# tube_power.net
KiCad netlist of a schematic drawn in EAGLE
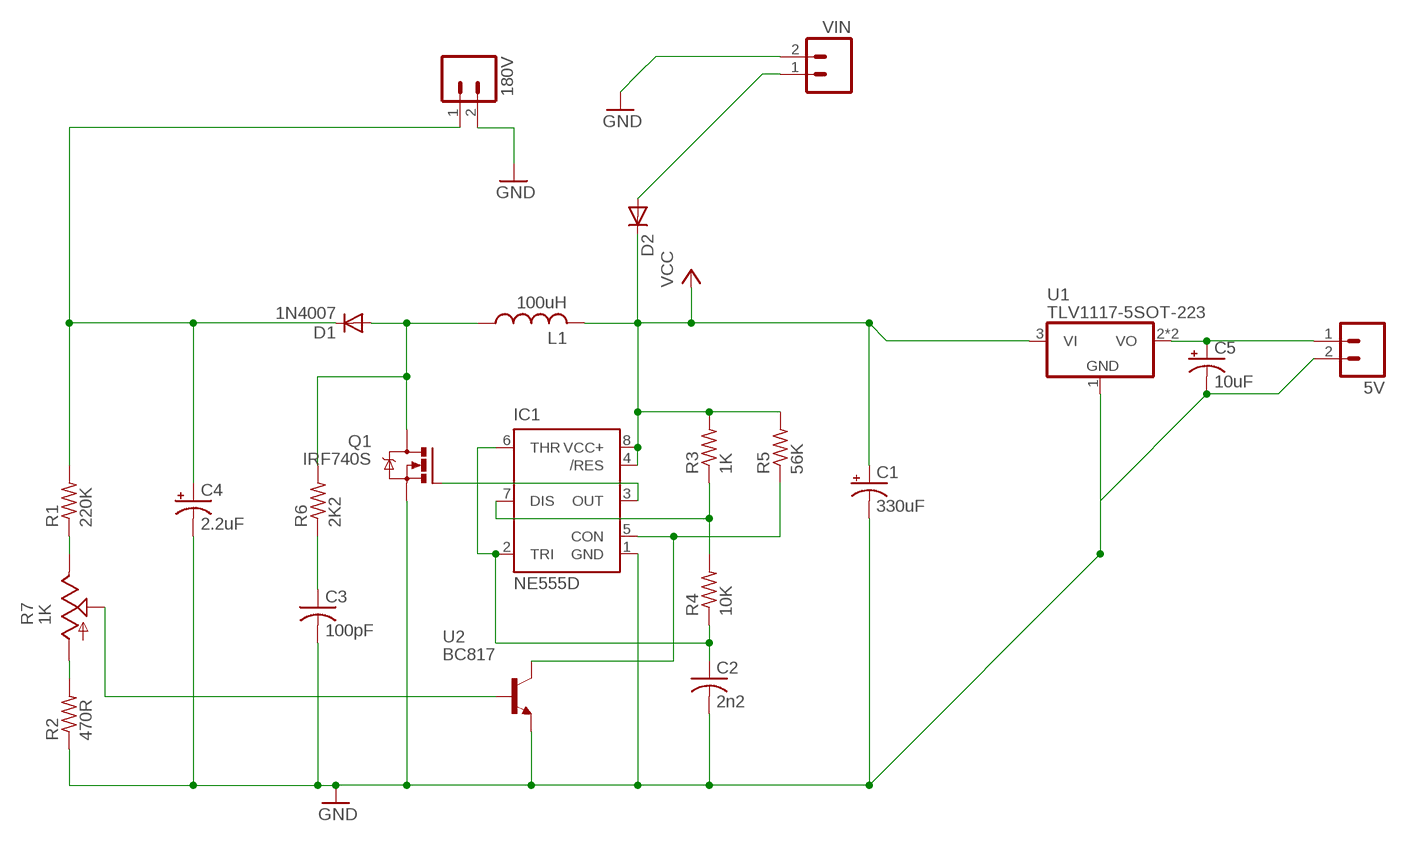
[diagram p0: schematic, sheet 1]

(export (version "E")
  (design (tool "Eeschema 10.0.6"))
  (components
    (comp (ref "5V")
      (value "M023.5MM")
      (footprint "eagle-import:SCREWTERMINAL-3.5MM-2")
      (libsource (lib "eagle-import") (part "M023.5MM"))
    )
    (comp (ref "180V")
      (value "M023.5MM")
      (footprint "eagle-import:SCREWTERMINAL-3.5MM-2")
      (libsource (lib "eagle-import") (part "M023.5MM"))
    )
    (comp (ref "C1")
      (value "330uF")
      (footprint "eagle-import:E5-10,5")
      (libsource (lib "eagle-import") (part "CAPACITOR_POLE5-10.5"))
    )
    (comp (ref "C2")
      (value "2n2")
      (footprint "eagle-import:C0805K")
      (libsource (lib "eagle-import") (part "CAPACITORC0805K"))
    )
    (comp (ref "C3")
      (value "100pF")
      (footprint "eagle-import:C0805K")
      (libsource (lib "eagle-import") (part "CAPACITORC0805K"))
    )
    (comp (ref "C4")
      (value "2.2uF")
      (footprint "eagle-import:E5-10,5")
      (libsource (lib "eagle-import") (part "CAPACITOR_POLE5-10.5"))
    )
    (comp (ref "C5")
      (value "10uF")
      (footprint "eagle-import:E2-5")
      (libsource (lib "eagle-import") (part "CAPACITOR_POLE2-5"))
    )
    (comp (ref "D1")
      (value "1N4007")
      (footprint "eagle-import:SMA-DIODE")
      (libsource (lib "eagle-import") (part "DIODESMA"))
    )
    (comp (ref "D2")
      (value "DIODESMA")
      (footprint "eagle-import:SMA-DIODE")
      (libsource (lib "eagle-import") (part "DIODESMA"))
    )
    (comp (ref "IC1")
      (value "NE555D")
      (footprint "eagle-import:SO08")
      (libsource (lib "eagle-import") (part "NE555D"))
    )
    (comp (ref "L1")
      (value "100uH")
      (footprint "eagle-import:RBL0712")
      (libsource (lib "eagle-import") (part "INDUCTOR"))
    )
    (comp (ref "Q1")
      (value "IRF740S")
      (footprint "eagle-import:TO263")
      (libsource (lib "eagle-import") (part "IRF740S"))
    )
    (comp (ref "R1")
      (value "220K")
      (footprint "eagle-import:0207_10")
      (libsource (lib "eagle-import") (part "RESISTOR0207/10"))
    )
    (comp (ref "R2")
      (value "470R")
      (footprint "eagle-import:0207_10")
      (libsource (lib "eagle-import") (part "RESISTOR0207/10"))
    )
    (comp (ref "R3")
      (value "1K")
      (footprint "eagle-import:R0805")
      (libsource (lib "eagle-import") (part "RESISTORR0805"))
    )
    (comp (ref "R4")
      (value "10K")
      (footprint "eagle-import:R0805")
      (libsource (lib "eagle-import") (part "RESISTORR0805"))
    )
    (comp (ref "R5")
      (value "56K")
      (footprint "eagle-import:R0805")
      (libsource (lib "eagle-import") (part "RESISTORR0805"))
    )
    (comp (ref "R6")
      (value "2K2")
      (footprint "eagle-import:R0805")
      (libsource (lib "eagle-import") (part "RESISTORR0805"))
    )
    (comp (ref "R7")
      (value "1K")
      (footprint "eagle-import:CA6V")
      (libsource (lib "eagle-import") (part "TRIM_POTCA6V"))
    )
    (comp (ref "U1")
      (value "TLV1117-5SOT-223")
      (footprint "eagle-import:SOT-223")
      (libsource (lib "eagle-import") (part "TLV1117-5SOT-223"))
    )
    (comp (ref "U2")
      (value "BC817")
      (footprint "eagle-import:SOT-23")
      (libsource (lib "eagle-import") (part "BC817"))
    )
    (comp (ref "VIN")
      (value "M023.5MM")
      (footprint "eagle-import:SCREWTERMINAL-3.5MM-2")
      (libsource (lib "eagle-import") (part "M023.5MM"))
    )
  )
  (nets
    (net (code "1") (name "GND") (class "Default")
      (node (ref "180V") (pin "2") (pinfunction "2_2") (pintype "passive"))
      (node (ref "5V") (pin "2") (pinfunction "2_2") (pintype "passive"))
      (node (ref "C1") (pin "-") (pinfunction "-_-") (pintype "passive"))
      (node (ref "C2") (pin "2") (pinfunction "2_2") (pintype "passive"))
      (node (ref "C3") (pin "2") (pinfunction "2_2") (pintype "passive"))
      (node (ref "C4") (pin "-") (pinfunction "-_-") (pintype "passive"))
      (node (ref "C5") (pin "-") (pinfunction "-_-") (pintype "passive"))
      (node (ref "IC1") (pin "1") (pinfunction "GND_1") (pintype "power_in"))
      (node (ref "Q1") (pin "2") (pinfunction "S_2") (pintype "passive"))
      (node (ref "R2") (pin "1") (pinfunction "1_1") (pintype "passive"))
      (node (ref "U1") (pin "1") (pinfunction "GND_1") (pintype "passive"))
      (node (ref "U2") (pin "2") (pinfunction "E_2") (pintype "passive"))
      (node (ref "VIN") (pin "2") (pinfunction "2_2") (pintype "passive"))
    )
    (net (code "2") (name "Net-(5V-Pad1)") (class "Default")
      (node (ref "5V") (pin "1") (pinfunction "1_1") (pintype "passive"))
      (node (ref "C5") (pin "+") (pinfunction "+_+") (pintype "passive"))
      (node (ref "U1") (pin "2") (pinfunction "VO_2") (pintype "passive"))
      (node (ref "U1") (pin "4") (pinfunction "VO_4") (pintype "passive"))
    )
    (net (code "3") (name "Net-(180V-Pad1)") (class "Default")
      (node (ref "180V") (pin "1") (pinfunction "1_1") (pintype "passive"))
      (node (ref "C4") (pin "+") (pinfunction "+_+") (pintype "passive"))
      (node (ref "D1") (pin "C") (pinfunction "C_C") (pintype "passive"))
      (node (ref "R1") (pin "2") (pinfunction "2_2") (pintype "passive"))
    )
    (net (code "4") (name "Net-(C3-Pad1)") (class "Default")
      (node (ref "C3") (pin "1") (pinfunction "1_1") (pintype "passive"))
      (node (ref "R6") (pin "1") (pinfunction "1_1") (pintype "passive"))
    )
    (net (code "5") (name "Net-(D2-PadA)") (class "Default")
      (node (ref "D2") (pin "A") (pinfunction "A_A") (pintype "passive"))
      (node (ref "VIN") (pin "1") (pinfunction "1_1") (pintype "passive"))
    )
    (net (code "6") (name "Net-(IC1-CON)") (class "Default")
      (node (ref "IC1") (pin "5") (pinfunction "CON_5") (pintype "input"))
      (node (ref "R5") (pin "1") (pinfunction "1_1") (pintype "passive"))
      (node (ref "U2") (pin "3") (pinfunction "C_3") (pintype "passive"))
    )
    (net (code "7") (name "Net-(IC1-DIS)") (class "Default")
      (node (ref "IC1") (pin "7") (pinfunction "DIS_7") (pintype "input"))
      (node (ref "R3") (pin "1") (pinfunction "1_1") (pintype "passive"))
      (node (ref "R4") (pin "2") (pinfunction "2_2") (pintype "passive"))
    )
    (net (code "8") (name "Net-(IC1-OUT)") (class "Default")
      (node (ref "IC1") (pin "3") (pinfunction "OUT_3") (pintype "output"))
      (node (ref "Q1") (pin "1") (pinfunction "G_1") (pintype "passive"))
    )
    (net (code "9") (name "Net-(IC1-THR)") (class "Default")
      (node (ref "C2") (pin "1") (pinfunction "1_1") (pintype "passive"))
      (node (ref "IC1") (pin "2") (pinfunction "TRI_2") (pintype "input"))
      (node (ref "IC1") (pin "6") (pinfunction "THR_6") (pintype "input"))
      (node (ref "R4") (pin "1") (pinfunction "1_1") (pintype "passive"))
    )
    (net (code "10") (name "Net-(L1-1)") (class "Default")
      (node (ref "D1") (pin "A") (pinfunction "A_A") (pintype "passive"))
      (node (ref "L1") (pin "P$1") (pinfunction "1_P$1") (pintype "passive"))
      (node (ref "Q1") (pin "3") (pinfunction "D_3") (pintype "passive"))
      (node (ref "R6") (pin "2") (pinfunction "2_2") (pintype "passive"))
    )
    (net (code "11") (name "Net-(R1-Pad1)") (class "Default")
      (node (ref "R1") (pin "1") (pinfunction "1_1") (pintype "passive"))
      (node (ref "R7") (pin "E") (pinfunction "E_E") (pintype "passive"))
    )
    (net (code "12") (name "Net-(R2-Pad2)") (class "Default")
      (node (ref "R2") (pin "2") (pinfunction "2_2") (pintype "passive"))
      (node (ref "R7") (pin "A") (pinfunction "A_A") (pintype "passive"))
    )
    (net (code "13") (name "Net-(U2-B)") (class "Default")
      (node (ref "R7") (pin "S") (pinfunction "S_S") (pintype "passive"))
      (node (ref "U2") (pin "1") (pinfunction "B_1") (pintype "passive"))
    )
    (net (code "14") (name "VCC") (class "Default")
      (node (ref "C1") (pin "+") (pinfunction "+_+") (pintype "passive"))
      (node (ref "D2") (pin "C") (pinfunction "C_C") (pintype "passive"))
      (node (ref "IC1") (pin "4") (pinfunction "/RES_4") (pintype "input"))
      (node (ref "IC1") (pin "8") (pinfunction "VCC+_8") (pintype "power_in"))
      (node (ref "L1") (pin "P$2") (pinfunction "2_P$2") (pintype "passive"))
      (node (ref "R3") (pin "2") (pinfunction "2_2") (pintype "passive"))
      (node (ref "R5") (pin "2") (pinfunction "2_2") (pintype "passive"))
      (node (ref "U1") (pin "3") (pinfunction "VI_3") (pintype "input"))
    )
  )
)
